# blink-a-led.net
KiCad netlist of a schematic drawn in EAGLE
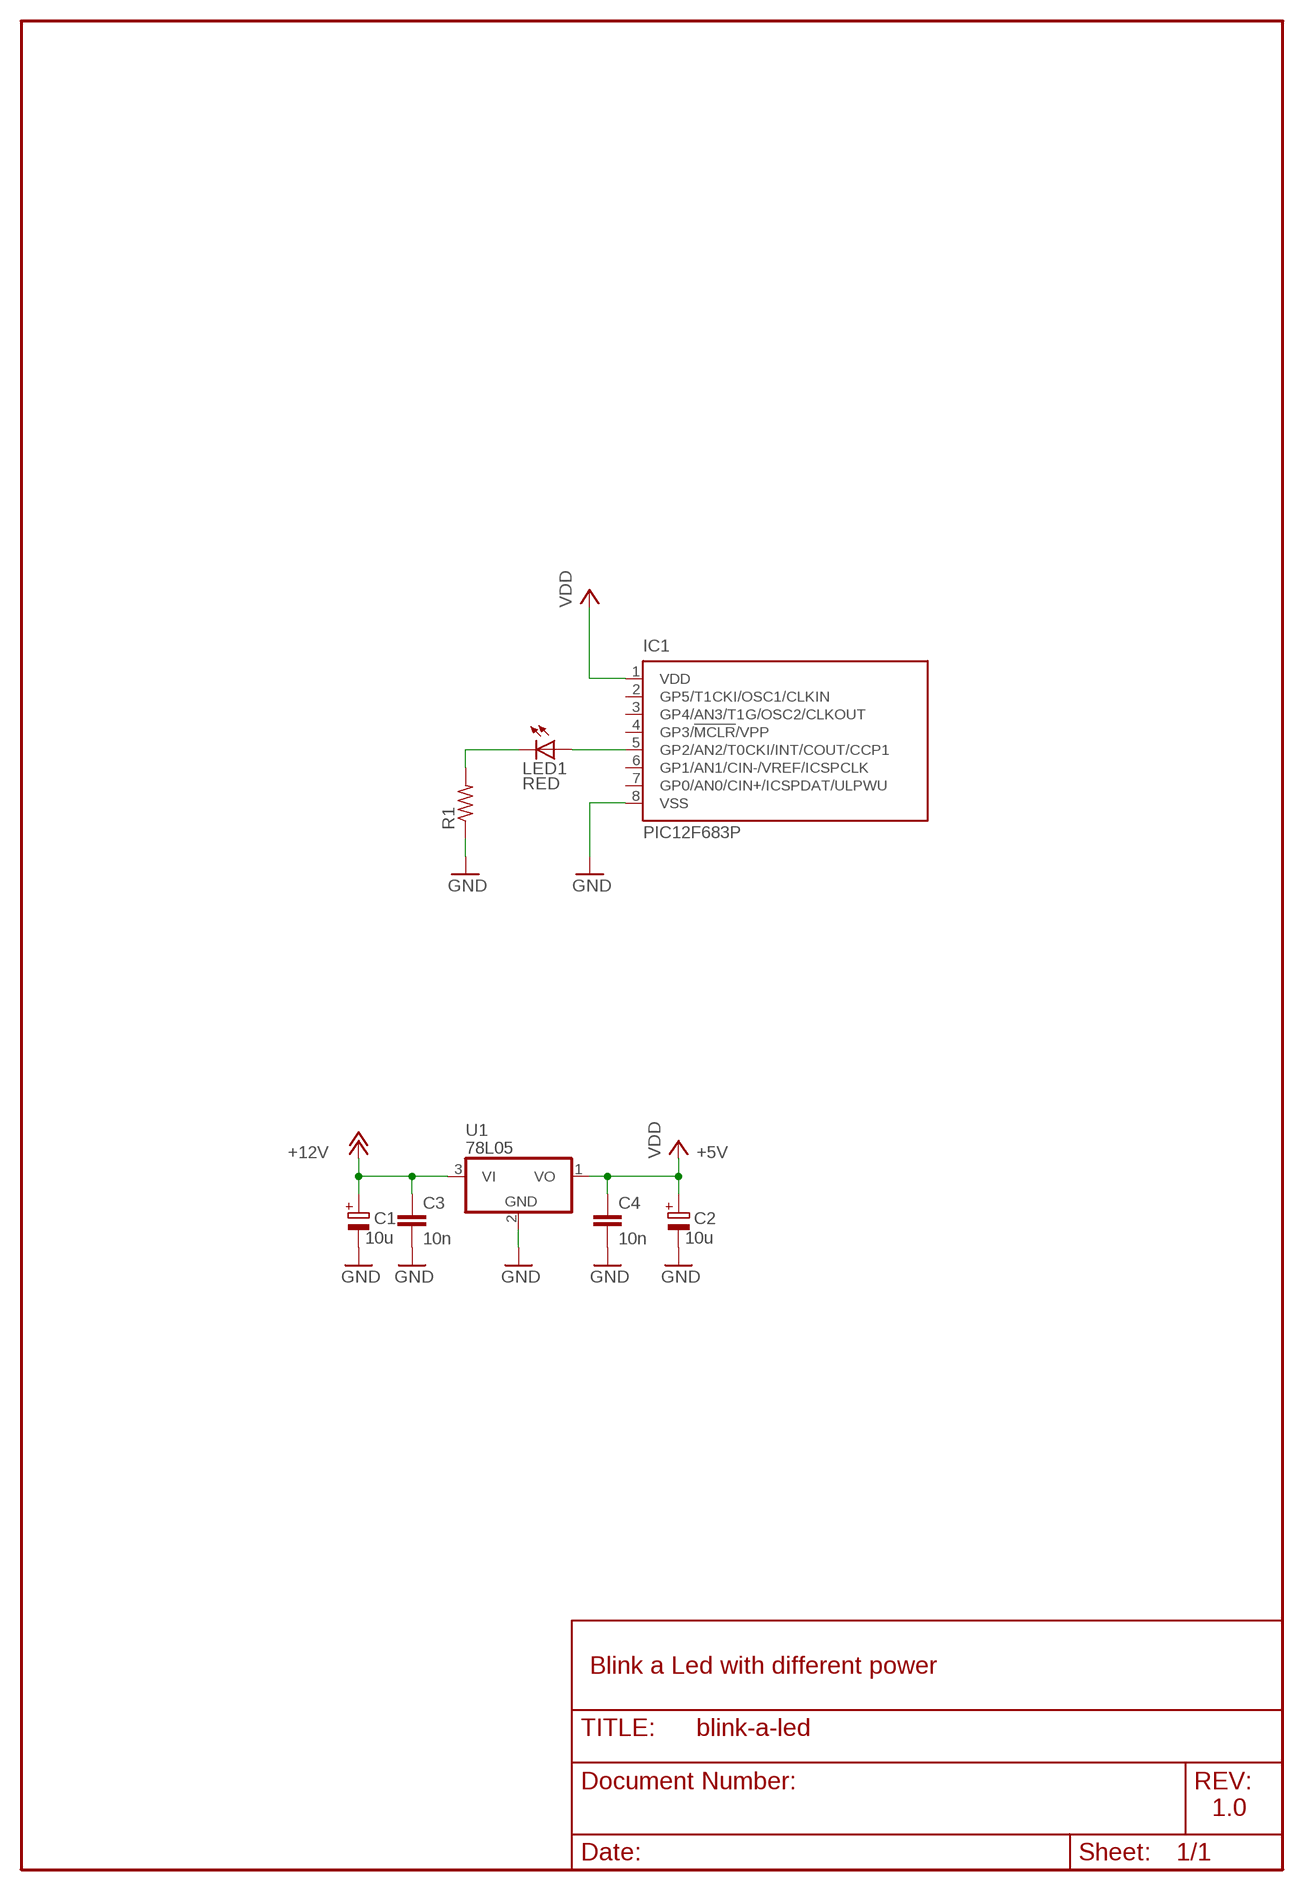
[diagram p0: schematic, sheet 1]

(export (version "E")
  (design (tool "Eeschema 10.0.6"))
  (components
    (comp (ref "C1")
      (value "10u")
      (footprint "eagle-import:E2,5-6")
      (libsource (lib "eagle-import") (part "E2,5-6"))
    )
    (comp (ref "C2")
      (value "10u")
      (footprint "eagle-import:E2,5-6")
      (libsource (lib "eagle-import") (part "E2,5-6"))
    )
    (comp (ref "C3")
      (value "10n")
      (footprint "eagle-import:C025-025X050")
      (libsource (lib "eagle-import") (part "C-EU025-025X050"))
    )
    (comp (ref "C4")
      (value "10n")
      (footprint "eagle-import:C025-025X050")
      (libsource (lib "eagle-import") (part "C-EU025-025X050"))
    )
    (comp (ref "IC1")
      (value "PIC12F683P")
      (footprint "eagle-import:DIL8")
      (fields (field (name "MF") "MICROCHIP") (field (name "MPN") "PIC12F683-I/P"))
      (libsource (lib "eagle-import") (part "PIC12F683P"))
    )
    (comp (ref "LED1")
      (value "RED")
      (footprint "eagle-import:LED5MM")
      (libsource (lib "eagle-import") (part "LED5MM"))
    )
    (comp (ref "R1")
      (value "R-US_0204/7")
      (footprint "eagle-import:0204_7")
      (libsource (lib "eagle-import") (part "R-US_0204/7"))
    )
    (comp (ref "U1")
      (value "78L05")
      (footprint "eagle-import:TO92")
      (libsource (lib "eagle-import") (part "78LXXZ"))
    )
  )
  (nets
    (net (code "1") (name "+12V") (class "Default")
      (node (ref "C1") (pin "+") (pinfunction "+_+") (pintype "passive"))
      (node (ref "C3") (pin "2") (pinfunction "2_2") (pintype "passive"))
      (node (ref "U1") (pin "3") (pinfunction "VI_3") (pintype "input"))
    )
    (net (code "2") (name "GND") (class "Default")
      (node (ref "C1") (pin "-") (pinfunction "-_-") (pintype "passive"))
      (node (ref "C2") (pin "-") (pinfunction "-_-") (pintype "passive"))
      (node (ref "C3") (pin "1") (pinfunction "1_1") (pintype "passive"))
      (node (ref "C4") (pin "1") (pinfunction "1_1") (pintype "passive"))
      (node (ref "IC1") (pin "8") (pinfunction "VSS_8") (pintype "power_in"))
      (node (ref "R1") (pin "1") (pinfunction "1_1") (pintype "passive"))
      (node (ref "U1") (pin "2") (pinfunction "GND_2") (pintype "passive"))
    )
    (net (code "3") (name "Net-(IC1-GP2{slash}AN2{slash}T0CKI{slash}INT{slash}COUT{slash}CCP1)") (class "Default")
      (node (ref "IC1") (pin "5") (pinfunction "GP2/AN2/T0CKI/INT/COUT/CCP1_5") (pintype "bidirectional"))
      (node (ref "LED1") (pin "A") (pinfunction "A_A") (pintype "passive"))
    )
    (net (code "4") (name "Net-(LED1-C)") (class "Default")
      (node (ref "LED1") (pin "K") (pinfunction "C_K") (pintype "passive"))
      (node (ref "R1") (pin "2") (pinfunction "2_2") (pintype "passive"))
    )
    (net (code "5") (name "VDD") (class "Default")
      (node (ref "C2") (pin "+") (pinfunction "+_+") (pintype "passive"))
      (node (ref "C4") (pin "2") (pinfunction "2_2") (pintype "passive"))
      (node (ref "IC1") (pin "1") (pinfunction "VDD_1") (pintype "power_in"))
      (node (ref "U1") (pin "1") (pinfunction "VO_1") (pintype "output"))
    )
    (net (code "6") (name "unconnected-(IC1-GP0{slash}AN0{slash}CIN+{slash}ICSPDAT{slash}ULPWU-Pad7)") (class "Default")
      (node (ref "IC1") (pin "7") (pinfunction "GP0/AN0/CIN+/ICSPDAT/ULPWU_7") (pintype "bidirectional"))
    )
    (net (code "7") (name "unconnected-(IC1-GP1{slash}AN1{slash}CIN-{slash}VREF{slash}ICSPCLK-Pad6)") (class "Default")
      (node (ref "IC1") (pin "6") (pinfunction "GP1/AN1/CIN-/VREF/ICSPCLK_6") (pintype "bidirectional"))
    )
    (net (code "8") (name "unconnected-(IC1-GP3{slash}~{MCLR}{slash}VPP-Pad4)") (class "Default")
      (node (ref "IC1") (pin "4") (pinfunction "GP3/~{MCLR}/VPP_4") (pintype "bidirectional"))
    )
    (net (code "9") (name "unconnected-(IC1-GP4{slash}AN3{slash}T1G{slash}OSC2{slash}CLKOUT-Pad3)") (class "Default")
      (node (ref "IC1") (pin "3") (pinfunction "GP4/AN3/T1G/OSC2/CLKOUT_3") (pintype "bidirectional"))
    )
    (net (code "10") (name "unconnected-(IC1-GP5{slash}T1CKI{slash}OSC1{slash}CLKIN-Pad2)") (class "Default")
      (node (ref "IC1") (pin "2") (pinfunction "GP5/T1CKI/OSC1/CLKIN_2") (pintype "bidirectional"))
    )
  )
)
